# placaESP-PORTA_LAR.net
KiCad netlist of a schematic drawn in EAGLE
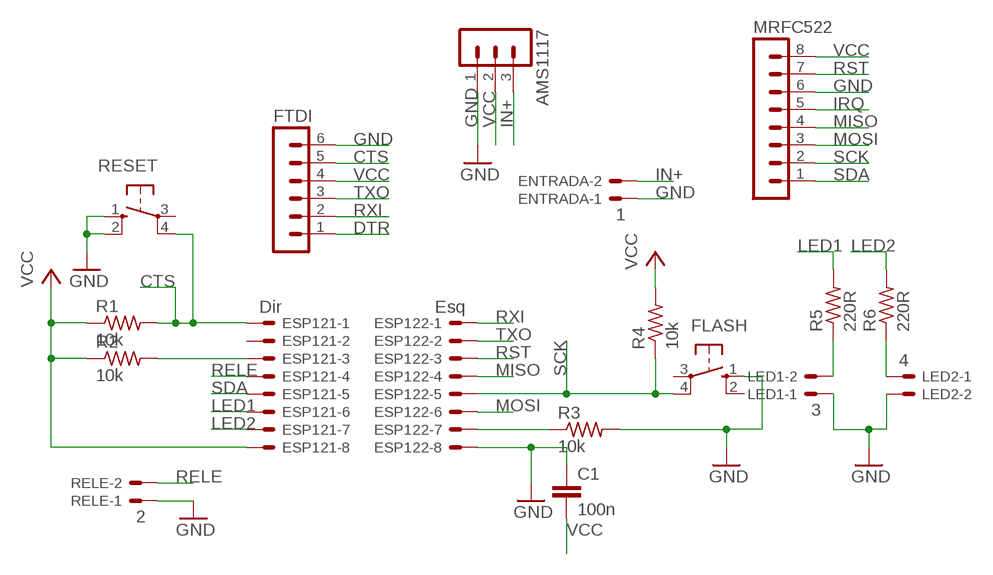
[diagram p0: schematic, sheet 1]

(export (version "E")
  (design (tool "Eeschema 10.0.6"))
  (components
    (comp (ref "AMS1117")
      (value "MA03-1")
      (footprint "eagle-import:MA03-1")
      (libsource (lib "eagle-import") (part "MA03-1"))
    )
    (comp (ref "C1")
      (value "100n")
      (footprint "eagle-import:C025-025X050")
      (libsource (lib "eagle-import") (part "C-EU025-025X050"))
    )
    (comp (ref "ENTRADA")
      (value "1")
      (footprint "eagle-import:22-23-2021")
      (fields (field (name "MF") "MOLEX") (field (name "MPN") "22-23-2021"))
      (libsource (lib "eagle-import") (part "22-23-2021"))
    )
    (comp (ref "ESP121")
      (value "Dir")
      (footprint "eagle-import:22-23-2081")
      (fields (field (name "MF") "MOLEX") (field (name "MPN") "22-23-2081"))
      (libsource (lib "eagle-import") (part "22-23-2081"))
    )
    (comp (ref "ESP122")
      (value "Esq")
      (footprint "eagle-import:22-23-2081")
      (fields (field (name "MF") "MOLEX") (field (name "MPN") "22-23-2081"))
      (libsource (lib "eagle-import") (part "22-23-2081"))
    )
    (comp (ref "FLASH")
      (value "10-XX")
      (footprint "eagle-import:B3F-10XX")
      (fields (field (name "MPN") "B3F-1000"))
      (libsource (lib "eagle-import") (part "10-XX"))
    )
    (comp (ref "FTDI")
      (value "MA06-1")
      (footprint "eagle-import:MA06-1")
      (libsource (lib "eagle-import") (part "MA06-1"))
    )
    (comp (ref "LED1")
      (value "3")
      (footprint "eagle-import:22-23-2021")
      (fields (field (name "MF") "MOLEX") (field (name "MPN") "22-23-2021"))
      (libsource (lib "eagle-import") (part "22-23-2021"))
    )
    (comp (ref "LED2")
      (value "4")
      (footprint "eagle-import:22-23-2021")
      (fields (field (name "MF") "MOLEX") (field (name "MPN") "22-23-2021"))
      (libsource (lib "eagle-import") (part "22-23-2021"))
    )
    (comp (ref "MRFC522")
      (value "MA08-1")
      (footprint "eagle-import:MA08-1")
      (libsource (lib "eagle-import") (part "MA08-1"))
    )
    (comp (ref "R1")
      (value "10k")
      (footprint "eagle-import:0207_10")
      (libsource (lib "eagle-import") (part "R-US_0207/10"))
    )
    (comp (ref "R2")
      (value "10k")
      (footprint "eagle-import:0207_10")
      (libsource (lib "eagle-import") (part "R-US_0207/10"))
    )
    (comp (ref "R3")
      (value "10k")
      (footprint "eagle-import:0207_10")
      (libsource (lib "eagle-import") (part "R-US_0207/10"))
    )
    (comp (ref "R4")
      (value "10k")
      (footprint "eagle-import:0207_10")
      (libsource (lib "eagle-import") (part "R-US_0207/10"))
    )
    (comp (ref "R5")
      (value "220R")
      (footprint "eagle-import:0207_10")
      (libsource (lib "eagle-import") (part "R-US_0207/10"))
    )
    (comp (ref "R6")
      (value "220R")
      (footprint "eagle-import:0207_10")
      (libsource (lib "eagle-import") (part "R-US_0207/10"))
    )
    (comp (ref "RELE")
      (value "2")
      (footprint "eagle-import:22-23-2021")
      (fields (field (name "MF") "MOLEX") (field (name "MPN") "22-23-2021"))
      (libsource (lib "eagle-import") (part "22-23-2021"))
    )
    (comp (ref "RESET")
      (value "10-XX")
      (footprint "eagle-import:B3F-10XX")
      (fields (field (name "MPN") "B3F-1000"))
      (libsource (lib "eagle-import") (part "10-XX"))
    )
  )
  (nets
    (net (code "1") (name "/CTS") (class "Default")
      (node (ref "ESP121") (pin "1") (pinfunction "S_1") (pintype "passive"))
      (node (ref "FTDI") (pin "5") (pinfunction "5_5") (pintype "passive"))
      (node (ref "R1") (pin "2") (pinfunction "2_2") (pintype "passive"))
      (node (ref "RESET") (pin "4") (pinfunction "P1_4") (pintype "passive"))
    )
    (net (code "2") (name "/DTR") (class "Default")
      (node (ref "FTDI") (pin "1") (pinfunction "1_1") (pintype "passive"))
    )
    (net (code "3") (name "/IN+") (class "Default")
      (node (ref "AMS1117") (pin "3") (pinfunction "3_3") (pintype "passive"))
      (node (ref "ENTRADA") (pin "2") (pinfunction "S_2") (pintype "passive"))
    )
    (net (code "4") (name "/IRQ") (class "Default")
      (node (ref "MRFC522") (pin "5") (pinfunction "5_5") (pintype "passive"))
    )
    (net (code "5") (name "/LED1") (class "Default")
      (node (ref "ESP121") (pin "6") (pinfunction "S_6") (pintype "passive"))
      (node (ref "R5") (pin "2") (pinfunction "2_2") (pintype "passive"))
    )
    (net (code "6") (name "/LED2") (class "Default")
      (node (ref "ESP121") (pin "7") (pinfunction "S_7") (pintype "passive"))
      (node (ref "R6") (pin "2") (pinfunction "2_2") (pintype "passive"))
    )
    (net (code "7") (name "/MISO") (class "Default")
      (node (ref "ESP122") (pin "4") (pinfunction "S_4") (pintype "passive"))
      (node (ref "MRFC522") (pin "4") (pinfunction "4_4") (pintype "passive"))
    )
    (net (code "8") (name "/MOSI") (class "Default")
      (node (ref "ESP122") (pin "6") (pinfunction "S_6") (pintype "passive"))
      (node (ref "MRFC522") (pin "3") (pinfunction "3_3") (pintype "passive"))
    )
    (net (code "9") (name "/RELE") (class "Default")
      (node (ref "ESP121") (pin "4") (pinfunction "S_4") (pintype "passive"))
      (node (ref "RELE") (pin "2") (pinfunction "S_2") (pintype "passive"))
    )
    (net (code "10") (name "/RST") (class "Default")
      (node (ref "ESP122") (pin "3") (pinfunction "S_3") (pintype "passive"))
      (node (ref "MRFC522") (pin "7") (pinfunction "7_7") (pintype "passive"))
    )
    (net (code "11") (name "/RXI") (class "Default")
      (node (ref "ESP122") (pin "1") (pinfunction "S_1") (pintype "passive"))
      (node (ref "FTDI") (pin "2") (pinfunction "2_2") (pintype "passive"))
    )
    (net (code "12") (name "/SCK") (class "Default")
      (node (ref "ESP122") (pin "5") (pinfunction "S_5") (pintype "passive"))
      (node (ref "FLASH") (pin "4") (pinfunction "P1_4") (pintype "passive"))
      (node (ref "MRFC522") (pin "2") (pinfunction "2_2") (pintype "passive"))
      (node (ref "R4") (pin "1") (pinfunction "1_1") (pintype "passive"))
    )
    (net (code "13") (name "/SDA") (class "Default")
      (node (ref "ESP121") (pin "5") (pinfunction "S_5") (pintype "passive"))
      (node (ref "MRFC522") (pin "1") (pinfunction "1_1") (pintype "passive"))
    )
    (net (code "14") (name "/TXO") (class "Default")
      (node (ref "ESP122") (pin "2") (pinfunction "S_2") (pintype "passive"))
      (node (ref "FTDI") (pin "3") (pinfunction "3_3") (pintype "passive"))
    )
    (net (code "15") (name "GND") (class "Default")
      (node (ref "AMS1117") (pin "1") (pinfunction "1_1") (pintype "passive"))
      (node (ref "C1") (pin "1") (pinfunction "1_1") (pintype "passive"))
      (node (ref "ENTRADA") (pin "1") (pinfunction "S_1") (pintype "passive"))
      (node (ref "ESP122") (pin "8") (pinfunction "S_8") (pintype "passive"))
      (node (ref "FLASH") (pin "1") (pinfunction "S_1") (pintype "passive"))
      (node (ref "FTDI") (pin "6") (pinfunction "6_6") (pintype "passive"))
      (node (ref "LED1") (pin "1") (pinfunction "S_1") (pintype "passive"))
      (node (ref "LED2") (pin "2") (pinfunction "S_2") (pintype "passive"))
      (node (ref "MRFC522") (pin "6") (pinfunction "6_6") (pintype "passive"))
      (node (ref "R3") (pin "2") (pinfunction "2_2") (pintype "passive"))
      (node (ref "RELE") (pin "1") (pinfunction "S_1") (pintype "passive"))
      (node (ref "RESET") (pin "1") (pinfunction "S_1") (pintype "passive"))
      (node (ref "RESET") (pin "2") (pinfunction "S1_2") (pintype "passive"))
    )
    (net (code "16") (name "Net-(ESP121C-S)") (class "Default")
      (node (ref "ESP121") (pin "3") (pinfunction "S_3") (pintype "passive"))
      (node (ref "R2") (pin "2") (pinfunction "2_2") (pintype "passive"))
    )
    (net (code "17") (name "Net-(ESP122G-S)") (class "Default")
      (node (ref "ESP122") (pin "7") (pinfunction "S_7") (pintype "passive"))
      (node (ref "R3") (pin "1") (pinfunction "1_1") (pintype "passive"))
    )
    (net (code "18") (name "Net-(LED1B-S)") (class "Default")
      (node (ref "LED1") (pin "2") (pinfunction "S_2") (pintype "passive"))
      (node (ref "R5") (pin "1") (pinfunction "1_1") (pintype "passive"))
    )
    (net (code "19") (name "Net-(LED2A-S)") (class "Default")
      (node (ref "LED2") (pin "1") (pinfunction "S_1") (pintype "passive"))
      (node (ref "R6") (pin "1") (pinfunction "1_1") (pintype "passive"))
    )
    (net (code "20") (name "VCC") (class "Default")
      (node (ref "AMS1117") (pin "2") (pinfunction "2_2") (pintype "passive"))
      (node (ref "C1") (pin "2") (pinfunction "2_2") (pintype "passive"))
      (node (ref "ESP121") (pin "8") (pinfunction "S_8") (pintype "passive"))
      (node (ref "FTDI") (pin "4") (pinfunction "4_4") (pintype "passive"))
      (node (ref "MRFC522") (pin "8") (pinfunction "8_8") (pintype "passive"))
      (node (ref "R1") (pin "1") (pinfunction "1_1") (pintype "passive"))
      (node (ref "R2") (pin "1") (pinfunction "1_1") (pintype "passive"))
      (node (ref "R4") (pin "2") (pinfunction "2_2") (pintype "passive"))
    )
    (net (code "21") (name "unconnected-(ESP121B-S-Pad2)") (class "Default")
      (node (ref "ESP121") (pin "2") (pinfunction "S_2") (pintype "passive"))
    )
    (net (code "22") (name "unconnected-(FLASH-P-Pad3)") (class "Default")
      (node (ref "FLASH") (pin "3") (pinfunction "P_3") (pintype "passive"))
    )
    (net (code "23") (name "unconnected-(FLASH-S1-Pad2)") (class "Default")
      (node (ref "FLASH") (pin "2") (pinfunction "S1_2") (pintype "passive"))
    )
    (net (code "24") (name "unconnected-(RESET-P-Pad3)") (class "Default")
      (node (ref "RESET") (pin "3") (pinfunction "P_3") (pintype "passive"))
    )
  )
)
